# 123_relay.net
KiCad netlist of a schematic drawn in EAGLE
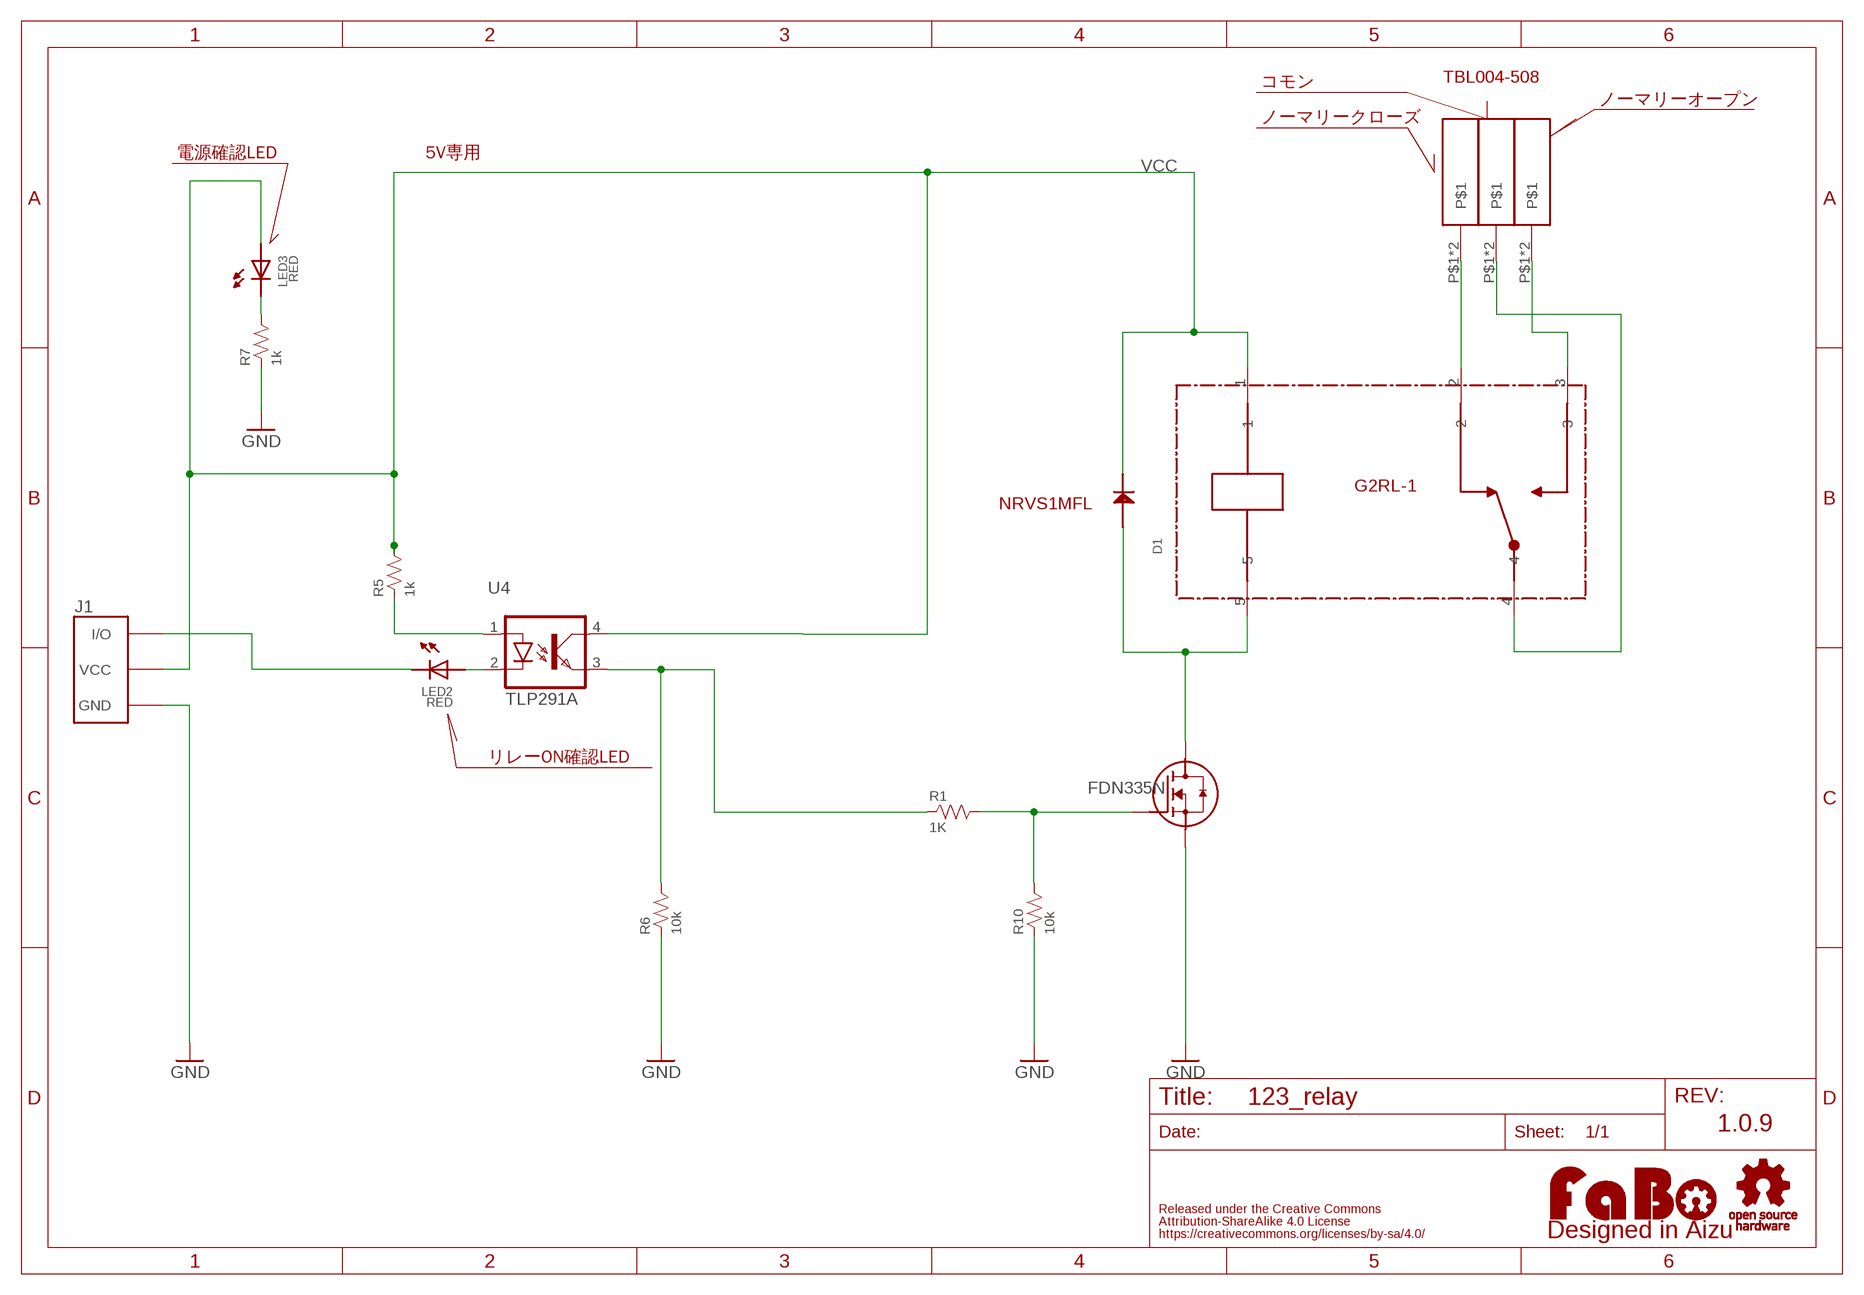
[diagram p0: schematic, sheet 1]

(export (version "E")
  (design (tool "Eeschema 10.0.6"))
  (components
    (comp (ref "D1")
      (value "NRVS1MFL")
      (footprint "eagle-import:SD-123F")
      (libsource (lib "eagle-import") (part "NRVS1MFL"))
    )
    (comp (ref "FET")
      (value "FDN335N")
      (footprint "eagle-import:FDN335")
      (libsource (lib "eagle-import") (part "FDN335N"))
    )
    (comp (ref "J1")
      (value "FABO_BRICK_3PIN-S03B-PASK-2_LONG")
      (footprint "eagle-import:FABO_BRICK_3PIN_S03B-PASK-2_LONG")
      (libsource (lib "eagle-import") (part "FABO_BRICK_3PIN-S03B-PASK-2_LONG"))
    )
    (comp (ref "LED2")
      (value "RED")
      (footprint "eagle-import:0603")
      (fields (field (name "SPICEPREFIX") "L"))
      (libsource (lib "eagle-import") (part "LED-0603"))
    )
    (comp (ref "LED3")
      (value "RED")
      (footprint "eagle-import:0603")
      (libsource (lib "eagle-import") (part "LED-0603"))
    )
    (comp (ref "LOGO1")
      (value "LOGO_FABO-M")
      (footprint "eagle-import:LOGO_FABO_M")
      (libsource (lib "eagle-import") (part "LOGO_FABO-M"))
    )
    (comp (ref "R1")
      (value "1K")
      (footprint "eagle-import:0603-NARROW")
      (libsource (lib "eagle-import") (part "RESISTOR-0603-NARROW"))
    )
    (comp (ref "R5")
      (value "1k")
      (footprint "eagle-import:0603-NARROW")
      (fields (field (name "SPICEPREFIX") "R"))
      (libsource (lib "eagle-import") (part "RESISTOR-0603-NARROW"))
    )
    (comp (ref "R6")
      (value "10k")
      (footprint "eagle-import:0603-NARROW")
      (libsource (lib "eagle-import") (part "RESISTOR-0603-NARROW"))
    )
    (comp (ref "R7")
      (value "1k")
      (footprint "eagle-import:0603-NARROW")
      (libsource (lib "eagle-import") (part "RESISTOR-0603-NARROW"))
    )
    (comp (ref "R10")
      (value "10k")
      (footprint "eagle-import:0603-NARROW")
      (libsource (lib "eagle-import") (part "RESISTOR-0603-NARROW"))
    )
    (comp (ref "U$2")
      (value "G2RL-1")
      (footprint "eagle-import:G2RL-1")
      (libsource (lib "eagle-import") (part "G2RL-1"))
    )
    (comp (ref "U$3")
      (value "TBL004-508")
      (footprint "eagle-import:TBL004-508")
      (libsource (lib "eagle-import") (part "TBL004-508"))
    )
    (comp (ref "U$4")
      (value "TBL004-508")
      (footprint "eagle-import:TBL004-508")
      (libsource (lib "eagle-import") (part "TBL004-508"))
    )
    (comp (ref "U$5")
      (value "TBL004-508")
      (footprint "eagle-import:TBL004-508")
      (libsource (lib "eagle-import") (part "TBL004-508"))
    )
    (comp (ref "U$10")
      (value "LOGO_OSHW-M_BOTTOM")
      (footprint "eagle-import:LOGO_OSHW_M_BOTTOM")
      (libsource (lib "eagle-import") (part "LOGO_OSHW-M_BOTTOM"))
    )
    (comp (ref "U4")
      (value "TLP291A")
      (footprint "eagle-import:11-3C1")
      (libsource (lib "eagle-import") (part "TLP291A"))
    )
  )
  (nets
    (net (code "1") (name "/VCC") (class "Default")
      (node (ref "D1") (pin "2") (pinfunction "CATHODE_2") (pintype "bidirectional"))
      (node (ref "J1") (pin "VCC") (pinfunction "VCC_VCC") (pintype "bidirectional"))
      (node (ref "LED3") (pin "ANODE") (pinfunction "ANODE_ANODE") (pintype "passive"))
      (node (ref "R5") (pin "2") (pinfunction "2_2") (pintype "bidirectional"))
      (node (ref "U$2") (pin "1") (pinfunction "1_1") (pintype "bidirectional"))
      (node (ref "U4") (pin "4") (pinfunction "COL_4") (pintype "passive"))
    )
    (net (code "2") (name "GND") (class "Default")
      (node (ref "FET") (pin "2:S") (pinfunction "S_2:S") (pintype "passive"))
      (node (ref "J1") (pin "GND") (pinfunction "GND_GND") (pintype "bidirectional"))
      (node (ref "R10") (pin "1") (pinfunction "1_1") (pintype "bidirectional"))
      (node (ref "R6") (pin "1") (pinfunction "1_1") (pintype "bidirectional"))
      (node (ref "R7") (pin "1") (pinfunction "1_1") (pintype "bidirectional"))
    )
    (net (code "3") (name "Net-(D1-ANODE)") (class "Default")
      (node (ref "D1") (pin "1") (pinfunction "ANODE_1") (pintype "bidirectional"))
      (node (ref "FET") (pin "3:D") (pinfunction "D_3:D") (pintype "passive"))
      (node (ref "U$2") (pin "5") (pinfunction "5_5") (pintype "bidirectional"))
    )
    (net (code "4") (name "Net-(FET-G)") (class "Default")
      (node (ref "FET") (pin "1:G") (pinfunction "G_1:G") (pintype "passive"))
      (node (ref "R1") (pin "2") (pinfunction "2_2") (pintype "bidirectional"))
      (node (ref "R10") (pin "2") (pinfunction "2_2") (pintype "bidirectional"))
    )
    (net (code "5") (name "Net-(J1-PadI{slash}O)") (class "Default")
      (node (ref "J1") (pin "I/O") (pinfunction "I/O_I/O") (pintype "bidirectional"))
      (node (ref "LED2") (pin "CATHODE") (pinfunction "CATHODE_CATHODE") (pintype "passive"))
    )
    (net (code "6") (name "Net-(LED3-PadCATHODE)") (class "Default")
      (node (ref "LED3") (pin "CATHODE") (pinfunction "CATHODE_CATHODE") (pintype "passive"))
      (node (ref "R7") (pin "2") (pinfunction "2_2") (pintype "bidirectional"))
    )
    (net (code "7") (name "Net-(U$2-Pad2)") (class "Default")
      (node (ref "U$2") (pin "2") (pinfunction "2_2") (pintype "bidirectional"))
      (node (ref "U$3") (pin "P$1") (pinfunction "P$1_P$1") (pintype "bidirectional"))
      (node (ref "U$3") (pin "P$2") (pinfunction "P$1_P$2") (pintype "bidirectional"))
    )
    (net (code "8") (name "Net-(U$2-Pad3)") (class "Default")
      (node (ref "U$2") (pin "3") (pinfunction "3_3") (pintype "bidirectional"))
      (node (ref "U$5") (pin "P$1") (pinfunction "P$1_P$1") (pintype "bidirectional"))
      (node (ref "U$5") (pin "P$2") (pinfunction "P$1_P$2") (pintype "bidirectional"))
    )
    (net (code "9") (name "Net-(U$2-Pad4)") (class "Default")
      (node (ref "U$2") (pin "4") (pinfunction "4_4") (pintype "bidirectional"))
      (node (ref "U$4") (pin "P$1") (pinfunction "P$1_P$1") (pintype "bidirectional"))
      (node (ref "U$4") (pin "P$2") (pinfunction "P$1_P$2") (pintype "bidirectional"))
    )
    (net (code "10") (name "Net-(U4-A)") (class "Default")
      (node (ref "R5") (pin "1") (pinfunction "1_1") (pintype "bidirectional"))
      (node (ref "U4") (pin "1") (pinfunction "A_1") (pintype "passive"))
    )
    (net (code "11") (name "Net-(U4-C)") (class "Default")
      (node (ref "LED2") (pin "ANODE") (pinfunction "ANODE_ANODE") (pintype "passive"))
      (node (ref "U4") (pin "2") (pinfunction "C_2") (pintype "passive"))
    )
    (net (code "12") (name "Net-(U4-EMI)") (class "Default")
      (node (ref "R1") (pin "1") (pinfunction "1_1") (pintype "bidirectional"))
      (node (ref "R6") (pin "2") (pinfunction "2_2") (pintype "bidirectional"))
      (node (ref "U4") (pin "3") (pinfunction "EMI_3") (pintype "passive"))
    )
  )
)
